# ECE445-Transmitter-Schematic-Oscillator.net
KiCad netlist of a schematic drawn in EAGLE
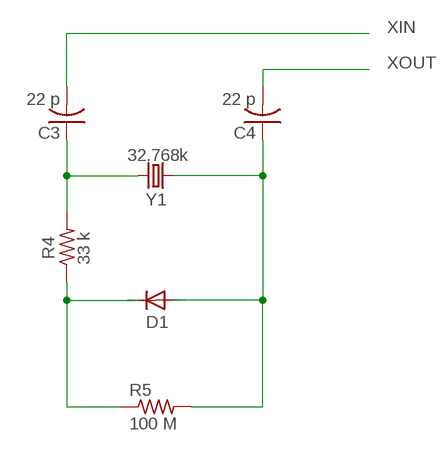
[diagram p0: schematic, sheet 1]

(export (version "E")
  (design (tool "Eeschema 10.0.6"))
  (components
    (comp (ref "C3")
      (value "22 p")
      (footprint "eagle-import:C025-024X044")
      (libsource (lib "eagle-import") (part "C-US025-024X044"))
    )
    (comp (ref "C4")
      (value "22 p")
      (footprint "eagle-import:C025-024X044")
      (libsource (lib "eagle-import") (part "C-US025-024X044"))
    )
    (comp (ref "D1")
      (value "1N4004")
      (footprint "eagle-import:DO41-10")
      (libsource (lib "eagle-import") (part "1N4004"))
    )
    (comp (ref "R4")
      (value "33 k")
      (footprint "eagle-import:0204V")
      (libsource (lib "eagle-import") (part "R-US_0204/2V"))
    )
    (comp (ref "R5")
      (value "100 M")
      (footprint "eagle-import:0204V")
      (libsource (lib "eagle-import") (part "R-US_0204/2V"))
    )
    (comp (ref "Y1")
      (value "32.768k")
      (footprint "eagle-import:CRYSTAL-32KHZ-SMD-MELF")
      (libsource (lib "eagle-import") (part "CRYSTAL32-SMD-MELF"))
    )
  )
  (nets
    (net (code "1") (name "/XIN") (class "Default")
      (node (ref "C3") (pin "2") (pinfunction "2_2") (pintype "passive"))
    )
    (net (code "2") (name "/XOUT") (class "Default")
      (node (ref "C4") (pin "2") (pinfunction "2_2") (pintype "passive"))
    )
    (net (code "3") (name "Net-(D1-PadC)") (class "Default")
      (node (ref "D1") (pin "C") (pinfunction "C_C") (pintype "passive"))
      (node (ref "R4") (pin "1") (pinfunction "1_1") (pintype "passive"))
      (node (ref "R5") (pin "1") (pinfunction "1_1") (pintype "passive"))
    )
    (net (code "4") (name "Net-(Y1-1)") (class "Default")
      (node (ref "C4") (pin "1") (pinfunction "1_1") (pintype "passive"))
      (node (ref "D1") (pin "A") (pinfunction "A_A") (pintype "passive"))
      (node (ref "R5") (pin "2") (pinfunction "2_2") (pintype "passive"))
      (node (ref "Y1") (pin "X1") (pinfunction "1_X1") (pintype "passive"))
    )
    (net (code "5") (name "Net-(Y1-2)") (class "Default")
      (node (ref "C3") (pin "1") (pinfunction "1_1") (pintype "passive"))
      (node (ref "R4") (pin "2") (pinfunction "2_2") (pintype "passive"))
      (node (ref "Y1") (pin "X2") (pinfunction "2_X2") (pintype "passive"))
    )
  )
)
